# MT3620AvnetModule.net
KiCad netlist of a schematic drawn in Altium Designer
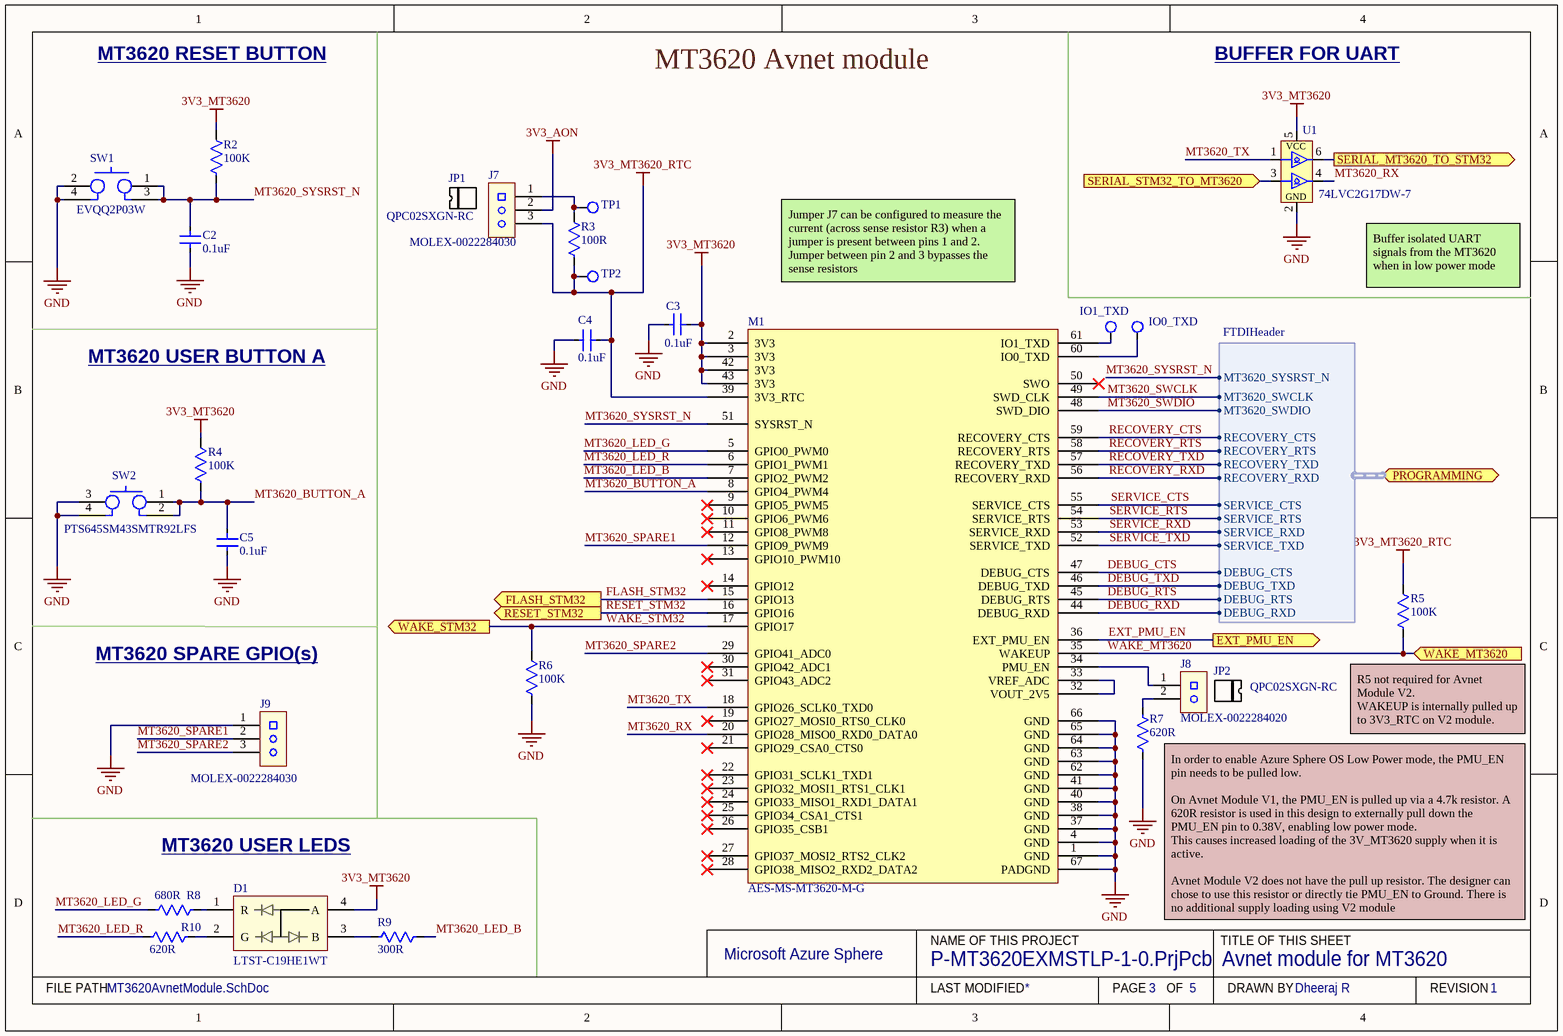
[diagram p0: MT3620AvnetModule.SchDoc]

(export (version "E")
  (design (tool "Eeschema 10.0.6"))
  (components
    (comp (ref "C2")
      (value "0.1uF")
      (footprint "CC0603")
      (description "0.1uF, 0603, CC0603KRX7R8BB104, Yageo, 25V, X7R, 10%, FULL REEL")
      (fields
        (field (name "MANUFACTURER") "Yageo")
        (field (name "MANUFACTURER PART NUMBER") "CC0603KRX7R8BB104")
      )
      (libsource (lib "Yageo") (part "CC0603KRX7R8BB104"))
    )
    (comp (ref "C3")
      (value "0.1uF")
      (footprint "CC0603")
      (description "0.1uF, 0603, CC0603KRX7R8BB104, Yageo, 25V, X7R, 10%, FULL REEL")
      (fields
        (field (name "MANUFACTURER") "Yageo")
        (field (name "MANUFACTURER PART NUMBER") "CC0603KRX7R8BB104")
      )
      (libsource (lib "Yageo") (part "CC0603KRX7R8BB104"))
    )
    (comp (ref "C4")
      (value "0.1uF")
      (footprint "CC0603")
      (description "0.1uF, 0603, CC0603KRX7R8BB104, Yageo, 25V, X7R, 10%, FULL REEL")
      (fields
        (field (name "MANUFACTURER") "Yageo")
        (field (name "MANUFACTURER PART NUMBER") "CC0603KRX7R8BB104")
      )
      (libsource (lib "Yageo") (part "CC0603KRX7R8BB104"))
    )
    (comp (ref "C5")
      (value "0.1uF")
      (footprint "CC0603")
      (description "0.1uF, 0603, CC0603KRX7R8BB104, Yageo, 25V, X7R, 10%, FULL REEL")
      (fields
        (field (name "MANUFACTURER") "Yageo")
        (field (name "MANUFACTURER PART NUMBER") "CC0603KRX7R8BB104")
      )
      (libsource (lib "Yageo") (part "CC0603KRX7R8BB104"))
    )
    (comp (ref "D1")
      (value "LTST-C19HE1WT")
      (footprint "LTST-C19HE1WT")
      (description "LED RGB DIFFUSED 0606 SMD")
      (fields (field (name "MANUFACTURER") "Lite-On Inc."))
      (libsource (lib "Lite-On") (part "LTST-C19HE1WT"))
    )
    (comp (ref "IO0_TXD")
      (value "TestPoint")
      (footprint "Pad1.27mm")
      (description "Test Point")
      (libsource (lib "generic") (part "TestPoint"))
    )
    (comp (ref "IO1_TXD")
      (value "TestPoint")
      (footprint "Pad1.27mm")
      (description "Test Point")
      (libsource (lib "generic") (part "TestPoint"))
    )
    (comp (ref "J7")
      (value "MOLEX-0022284030")
      (footprint "0022284030")
      (description "CONN HEADER 3POS .100 VERT TIN")
      (fields
        (field (name "MANUFACTURER") "Molex, LLC")
        (field (name "MANUFACTURER PART NUMBER") "0022284030")
      )
      (libsource (lib "") (part "MOLEX-0022284030_1"))
    )
    (comp (ref "J8")
      (value "MOLEX-0022284020")
      (footprint "0022284020")
      (description "CONN HEADER 2POS .100 VERT TIN")
      (fields
        (field (name "MANUFACTURER") "Molex, LLC")
        (field (name "MANUFACTURER PART NUMBER") "0022284020")
      )
      (libsource (lib "Molex") (part "MOLEX-0022284020"))
    )
    (comp (ref "J9")
      (value "MOLEX-0022284030")
      (footprint "0022284030")
      (description "CONN HEADER 3POS .100 VERT TIN")
      (fields
        (field (name "MANUFACTURER") "Molex, LLC")
        (field (name "MANUFACTURER PART NUMBER") "0022284030")
      )
      (libsource (lib "Molex") (part "MOLEX-0022284030"))
    )
    (comp (ref "JP1")
      (value "QPC02SXGN-RC")
      (description "CONN JUMPER SHORTING .100\" GOLD")
      (fields (field (name "MANUFACTURER") "Sullins"))
      (libsource (lib "") (part "QPC02SXGN-RC_1"))
    )
    (comp (ref "JP2")
      (value "QPC02SXGN-RC")
      (description "CONN JUMPER SHORTING .100\" GOLD")
      (fields (field (name "MANUFACTURER") "Sullins"))
      (libsource (lib "SullinsConnectorSolutions") (part "QPC02SXGN-RC"))
    )
    (comp (ref "M1")
      (value "AES-MS-MT3620-M-G")
      (footprint "AES-MS-MT3620-M-G")
      (libsource (lib "Avnet") (part "AES-MS-MT3620-M-G (SAT)"))
    )
    (comp (ref "R2")
      (value "100K")
      (footprint "VISHAY-0603")
      (description "100K Ohm 0603 1% 0.1W(1/10W) 100ppm Paper T/R")
      (fields
        (field (name "MANUFACTURER") "Yageo")
        (field (name "MANUFACTURER PART NUMBER") "RC0603FR-07100KL")
      )
      (libsource (lib "Yageo") (part "RC0603FR-07100KL"))
    )
    (comp (ref "R3")
      (value "100R")
      (footprint "VISHAY-0603")
      (description "100 OHM Current Sense 0.1% 1/2W 0603")
      (fields
        (field (name "MANUFACTURER") "Vishay Dale Thin Film")
        (field (name "MANUFACTURER PART NUMBER") "PCAN0603E1000BST5")
      )
      (libsource (lib "Vishay") (part "PCAN0603E1000BST5"))
    )
    (comp (ref "R4")
      (value "100K")
      (footprint "VISHAY-0603")
      (description "100K Ohm 0603 1% 0.1W(1/10W) 100ppm Paper T/R")
      (fields
        (field (name "MANUFACTURER") "Yageo")
        (field (name "MANUFACTURER PART NUMBER") "RC0603FR-07100KL")
      )
      (libsource (lib "Yageo") (part "RC0603FR-07100KL"))
    )
    (comp (ref "R5")
      (value "100K")
      (footprint "VISHAY-0603")
      (description "100K Ohm 0603 1% 0.1W(1/10W) 100ppm Paper T/R")
      (fields
        (field (name "MANUFACTURER") "Yageo")
        (field (name "MANUFACTURER PART NUMBER") "RC0603FR-07100KL")
      )
      (libsource (lib "Yageo") (part "RC0603FR-07100KL"))
    )
    (comp (ref "R6")
      (value "100K")
      (footprint "VISHAY-0603")
      (description "100K Ohm 0603 1% 0.1W(1/10W) 100ppm Paper T/R")
      (fields
        (field (name "MANUFACTURER") "Yageo")
        (field (name "MANUFACTURER PART NUMBER") "RC0603FR-07100KL")
      )
      (libsource (lib "Yageo") (part "RC0603FR-07100KL"))
    )
    (comp (ref "R7")
      (value "620R")
      (footprint "RC0603")
      (description "620 Ohm, 0603, 1% 0.1W(1/10W) 100ppm/ C Molded SMD Paper T/R")
      (fields
        (field (name "MANUFACTURER") "Yageo")
        (field (name "MANUFACTURER PART NUMBER") "RC0603FR-07620RL")
      )
      (libsource (lib "Yageo") (part "RC0603FR-07620RL"))
    )
    (comp (ref "R8")
      (value "680R")
      (footprint "RC0603")
      (description "680R, 0603 YAGEO - RC0603FR-07680RL - SMD Chip Resistor, RC Series, 50 V, Thick Film, 100 mW")
      (fields
        (field (name "MANUFACTURER") "Yageo")
        (field (name "MANUFACTURER PART NUMBER") "RC0603FR-07680RL")
      )
      (libsource (lib "Yageo") (part "RC0603FR-07680RL"))
    )
    (comp (ref "R9")
      (value "300R")
      (footprint "RC0603")
      (description "300 Ohm, 0603, 1% 0.1W(1/10W) 100ppm/ C Molded SMD Paper T/R")
      (fields
        (field (name "MANUFACTURER") "Yageo")
        (field (name "MANUFACTURER PART NUMBER") "RC0603FR-07300RL")
      )
      (libsource (lib "Yageo") (part "RC0603FR-07300RL"))
    )
    (comp (ref "R10")
      (value "620R")
      (footprint "RC0603")
      (description "620 Ohm, 0603, 1% 0.1W(1/10W) 100ppm/ C Molded SMD Paper T/R")
      (fields
        (field (name "MANUFACTURER") "Yageo")
        (field (name "MANUFACTURER PART NUMBER") "RC0603FR-07620RL")
      )
      (libsource (lib "Yageo") (part "RC0603FR-07620RL"))
    )
    (comp (ref "SW1")
      (value "SWI TACT SPN0 PANASONIC EVQQ2P03W")
      (footprint "EVQQ2P03W")
      (description "PANASONIC - EVQQ2P03W - SWITCH, SPNO, SMD")
      (fields (field (name "MANUFACTURER") "PANASONIC") (field (name "MANUFACTURER PART NUMBER") "EVQQ2P03W"))
      (libsource (lib "switch") (part "SWI TACT SPN0 PANASONIC EVQQ2P03W"))
    )
    (comp (ref "SW2")
      (value "PTS645SM43SMTR92LFS")
      (footprint "C&K PTS645SM43SMTR92LFS")
      (description "SWITCH TACTILE SPST-NO 0.05A 12V")
      (fields (field (name "MANUFACTURER") "ITT C&K"))
      (libsource (lib "C&K") (part "PTS645SM43SMTR92LFS"))
    )
    (comp (ref "TP1")
      (value "TestPointHole")
      (footprint "PTH1.27mm-0.9mm")
      (description "Test Point With Hole")
      (libsource (lib "generic") (part "TestPointHole"))
    )
    (comp (ref "TP2")
      (value "TestPointHole")
      (footprint "PTH1.27mm-0.9mm")
      (description "Test Point With Hole")
      (libsource (lib "generic") (part "TestPointHole"))
    )
    (comp (ref "U1")
      (value "74LVC2G17DW-7")
      (footprint "Nexperia-SOT363")
      (description "Buffers & Line Drivers LVC 2 Gates LOGIC")
      (fields (field (name "MANUFACTURER") "Diodes"))
      (libsource (lib "DiodesInc") (part "74LVC2G17DW-7"))
    )
  )
  (nets
    (net (code "2") (name "/DEBUG_CTS") (class "Default")
      (node (ref "M1") (pin "47") (pinfunction "DEBUG_CTS_47") (pintype "passive"))
    )
    (net (code "3") (name "/DEBUG_RTS") (class "Default")
      (node (ref "M1") (pin "45") (pinfunction "DEBUG_RTS_45") (pintype "passive"))
    )
    (net (code "4") (name "/DEBUG_RXD") (class "Default")
      (node (ref "M1") (pin "44") (pinfunction "DEBUG_RXD_44") (pintype "passive"))
    )
    (net (code "5") (name "/DEBUG_TXD") (class "Default")
      (node (ref "M1") (pin "46") (pinfunction "DEBUG_TXD_46") (pintype "passive"))
    )
    (net (code "6") (name "/EXT_PMU_EN") (class "Default")
      (node (ref "M1") (pin "36") (pinfunction "EXT_PMU_EN_36") (pintype "passive"))
    )
    (net (code "7") (name "/FLASH_STM32") (class "Default")
      (node (ref "M1") (pin "15") (pinfunction "GPIO13_15") (pintype "passive"))
    )
    (net (code "8") (name "/MT3620_BUTTON_A") (class "Default")
      (node (ref "C5") (pin "2") (pinfunction "2_2") (pintype "passive"))
      (node (ref "M1") (pin "8") (pinfunction "GPIO4_PWM4_8") (pintype "passive"))
      (node (ref "R4") (pin "1") (pinfunction "1_1") (pintype "passive"))
      (node (ref "SW2") (pin "1") (pinfunction "1_1") (pintype "passive"))
      (node (ref "SW2") (pin "2") (pinfunction "2_2") (pintype "passive"))
    )
    (net (code "9") (name "/MT3620_LED_B") (class "Default")
      (node (ref "M1") (pin "7") (pinfunction "GPIO2_PWM2_7") (pintype "passive"))
      (node (ref "R9") (pin "2") (pinfunction "2_2") (pintype "passive"))
    )
    (net (code "10") (name "/MT3620_LED_G") (class "Default")
      (node (ref "M1") (pin "5") (pinfunction "GPIO0_PWM0_5") (pintype "passive"))
      (node (ref "R8") (pin "1") (pinfunction "1_1") (pintype "passive"))
    )
    (net (code "11") (name "/MT3620_LED_R") (class "Default")
      (node (ref "M1") (pin "6") (pinfunction "GPIO1_PWM1_6") (pintype "passive"))
      (node (ref "R10") (pin "1") (pinfunction "1_1") (pintype "passive"))
    )
    (net (code "12") (name "/MT3620_RX") (class "Default")
      (node (ref "M1") (pin "20") (pinfunction "GPIO28_MISO0_RXD0_DATA0_20") (pintype "passive"))
      (node (ref "U1") (pin "4") (pinfunction "4_4") (pintype "passive"))
    )
    (net (code "13") (name "/MT3620_SPARE1") (class "Default")
      (node (ref "J9") (pin "2") (pinfunction "2_2") (pintype "passive"))
      (node (ref "M1") (pin "12") (pinfunction "GPIO9_PWM9_12") (pintype "passive"))
    )
    (net (code "14") (name "/MT3620_SPARE2") (class "Default")
      (node (ref "J9") (pin "3") (pinfunction "3_3") (pintype "passive"))
      (node (ref "M1") (pin "29") (pinfunction "GPIO41_ADC0_29") (pintype "passive"))
    )
    (net (code "15") (name "/MT3620_SWCLK") (class "Default")
      (node (ref "M1") (pin "49") (pinfunction "SWD_CLK_49") (pintype "passive"))
    )
    (net (code "16") (name "/MT3620_SWDIO") (class "Default")
      (node (ref "M1") (pin "48") (pinfunction "SWD_DIO_48") (pintype "passive"))
    )
    (net (code "17") (name "/MT3620_SYSRST_N") (class "Default")
      (node (ref "C2") (pin "2") (pinfunction "2_2") (pintype "passive"))
      (node (ref "M1") (pin "51") (pinfunction "SYSRST_N_51") (pintype "passive"))
      (node (ref "R2") (pin "1") (pinfunction "1_1") (pintype "passive"))
      (node (ref "SW1") (pin "1") (pinfunction "1_1") (pintype "passive"))
      (node (ref "SW1") (pin "3") (pinfunction "3_3") (pintype "passive"))
    )
    (net (code "18") (name "/MT3620_TX") (class "Default")
      (node (ref "M1") (pin "18") (pinfunction "GPIO26_SCLK0_TXD0_18") (pintype "passive"))
      (node (ref "U1") (pin "1") (pinfunction "1_1") (pintype "passive"))
    )
    (net (code "19") (name "/RECOVERY_CTS") (class "Default")
      (node (ref "M1") (pin "59") (pinfunction "RECOVERY_CTS_59") (pintype "passive"))
    )
    (net (code "20") (name "/RECOVERY_RTS") (class "Default")
      (node (ref "M1") (pin "58") (pinfunction "RECOVERY_RTS_58") (pintype "passive"))
    )
    (net (code "21") (name "/RECOVERY_RXD") (class "Default")
      (node (ref "M1") (pin "56") (pinfunction "RECOVERY_RXD_56") (pintype "passive"))
    )
    (net (code "22") (name "/RECOVERY_TXD") (class "Default")
      (node (ref "M1") (pin "57") (pinfunction "RECOVERY_TXD_57") (pintype "passive"))
    )
    (net (code "23") (name "/RESET_STM32") (class "Default")
      (node (ref "M1") (pin "16") (pinfunction "GPIO16_16") (pintype "passive"))
    )
    (net (code "24") (name "/SERIAL_MT3620_TO_STM32") (class "Default")
      (node (ref "U1") (pin "6") (pinfunction "6_6") (pintype "passive"))
    )
    (net (code "25") (name "/SERIAL_STM32_TO_MT3620") (class "Default")
      (node (ref "U1") (pin "3") (pinfunction "3_3") (pintype "passive"))
    )
    (net (code "26") (name "/SERVICE_CTS") (class "Default")
      (node (ref "M1") (pin "55") (pinfunction "SERVICE_CTS_55") (pintype "passive"))
    )
    (net (code "27") (name "/SERVICE_RTS") (class "Default")
      (node (ref "M1") (pin "54") (pinfunction "SERVICE_RTS_54") (pintype "passive"))
    )
    (net (code "28") (name "/SERVICE_RXD") (class "Default")
      (node (ref "M1") (pin "53") (pinfunction "SERVICE_RXD_53") (pintype "passive"))
    )
    (net (code "29") (name "/SERVICE_TXD") (class "Default")
      (node (ref "M1") (pin "52") (pinfunction "SERVICE_TXD_52") (pintype "passive"))
    )
    (net (code "30") (name "/WAKE_MT3620") (class "Default")
      (node (ref "M1") (pin "35") (pinfunction "WAKEUP_35") (pintype "passive"))
      (node (ref "R5") (pin "1") (pinfunction "1_1") (pintype "passive"))
    )
    (net (code "31") (name "/WAKE_STM32") (class "Default")
      (node (ref "M1") (pin "17") (pinfunction "GPIO17_17") (pintype "passive"))
      (node (ref "R6") (pin "2") (pinfunction "2_2") (pintype "passive"))
    )
    (net (code "33") (name "3V3_AON") (class "Default")
      (node (ref "J7") (pin "2") (pinfunction "2_2") (pintype "passive"))
    )
    (net (code "34") (name "3V3_MT3620") (class "Default")
      (node (ref "C3") (pin "2") (pinfunction "2_2") (pintype "passive"))
      (node (ref "D1") (pin "4") (pinfunction "A_4") (pintype "passive"))
      (node (ref "M1") (pin "2") (pinfunction "3V3_2") (pintype "passive"))
      (node (ref "M1") (pin "3") (pinfunction "3V3_3") (pintype "passive"))
      (node (ref "M1") (pin "42") (pinfunction "3V3_42") (pintype "passive"))
      (node (ref "M1") (pin "43") (pinfunction "3V3_43") (pintype "passive"))
      (node (ref "R2") (pin "2") (pinfunction "2_2") (pintype "passive"))
      (node (ref "R4") (pin "2") (pinfunction "2_2") (pintype "passive"))
      (node (ref "U1") (pin "5") (pinfunction "5_5") (pintype "passive"))
    )
    (net (code "35") (name "3V3_MT3620_RTC") (class "Default")
      (node (ref "C4") (pin "2") (pinfunction "2_2") (pintype "passive"))
      (node (ref "J7") (pin "3") (pinfunction "3_3") (pintype "passive"))
      (node (ref "M1") (pin "39") (pinfunction "3V3_RTC_39") (pintype "passive"))
      (node (ref "R3") (pin "2") (pinfunction "2_2") (pintype "passive"))
      (node (ref "R5") (pin "2") (pinfunction "2_2") (pintype "passive"))
      (node (ref "TP2") (pin "1") (pinfunction "1_1") (pintype "passive"))
    )
    (net (code "36") (name "GND") (class "Default")
      (node (ref "C2") (pin "1") (pinfunction "1_1") (pintype "passive"))
      (node (ref "C3") (pin "1") (pinfunction "1_1") (pintype "passive"))
      (node (ref "C4") (pin "1") (pinfunction "1_1") (pintype "passive"))
      (node (ref "C5") (pin "1") (pinfunction "1_1") (pintype "passive"))
      (node (ref "J9") (pin "1") (pinfunction "1_1") (pintype "passive"))
      (node (ref "M1") (pin "1") (pinfunction "GND_1") (pintype "passive"))
      (node (ref "M1") (pin "37") (pinfunction "GND_37") (pintype "passive"))
      (node (ref "M1") (pin "38") (pinfunction "GND_38") (pintype "passive"))
      (node (ref "M1") (pin "4") (pinfunction "GND_4") (pintype "passive"))
      (node (ref "M1") (pin "40") (pinfunction "GND_40") (pintype "passive"))
      (node (ref "M1") (pin "41") (pinfunction "GND_41") (pintype "passive"))
      (node (ref "M1") (pin "62") (pinfunction "GND_62") (pintype "passive"))
      (node (ref "M1") (pin "63") (pinfunction "GND_63") (pintype "passive"))
      (node (ref "M1") (pin "64") (pinfunction "GND_64") (pintype "passive"))
      (node (ref "M1") (pin "65") (pinfunction "GND_65") (pintype "passive"))
      (node (ref "M1") (pin "66") (pinfunction "GND_66") (pintype "passive"))
      (node (ref "M1") (pin "67") (pinfunction "PADGND_67") (pintype "passive"))
      (node (ref "R6") (pin "1") (pinfunction "1_1") (pintype "passive"))
      (node (ref "R7") (pin "1") (pinfunction "1_1") (pintype "passive"))
      (node (ref "SW1") (pin "2") (pinfunction "2_2") (pintype "passive"))
      (node (ref "SW1") (pin "4") (pinfunction "4_4") (pintype "passive"))
      (node (ref "SW2") (pin "3") (pinfunction "3_3") (pintype "passive"))
      (node (ref "SW2") (pin "4") (pinfunction "4_4") (pintype "passive"))
      (node (ref "U1") (pin "2") (pinfunction "2_2") (pintype "passive"))
    )
    (net (code "37") (name "Net-(D1-B)") (class "Default")
      (node (ref "D1") (pin "3") (pinfunction "B_3") (pintype "passive"))
      (node (ref "R9") (pin "1") (pinfunction "1_1") (pintype "passive"))
    )
    (net (code "38") (name "Net-(D1-G)") (class "Default")
      (node (ref "D1") (pin "2") (pinfunction "G_2") (pintype "passive"))
      (node (ref "R10") (pin "2") (pinfunction "2_2") (pintype "passive"))
    )
    (net (code "39") (name "Net-(D1-R)") (class "Default")
      (node (ref "D1") (pin "1") (pinfunction "R_1") (pintype "passive"))
      (node (ref "R8") (pin "2") (pinfunction "2_2") (pintype "passive"))
    )
    (net (code "40") (name "Net-(J7-Pad1)") (class "Default")
      (node (ref "J7") (pin "1") (pinfunction "1_1") (pintype "passive"))
      (node (ref "R3") (pin "1") (pinfunction "1_1") (pintype "passive"))
      (node (ref "TP1") (pin "1") (pinfunction "1_1") (pintype "passive"))
    )
    (net (code "41") (name "Net-(J8-Pad2)") (class "Default")
      (node (ref "J8") (pin "2") (pinfunction "2_2") (pintype "passive"))
      (node (ref "R7") (pin "2") (pinfunction "2_2") (pintype "passive"))
    )
    (net (code "42") (name "Net-(M1-IO0_TXD)") (class "Default")
      (node (ref "IO0_TXD") (pin "1") (pinfunction "1_1") (pintype "passive"))
      (node (ref "M1") (pin "60") (pinfunction "IO0_TXD_60") (pintype "passive"))
    )
    (net (code "43") (name "Net-(M1-IO1_TXD)") (class "Default")
      (node (ref "IO1_TXD") (pin "1") (pinfunction "1_1") (pintype "passive"))
      (node (ref "M1") (pin "61") (pinfunction "IO1_TXD_61") (pintype "passive"))
    )
    (net (code "44") (name "Net-(M1-PMU_EN)") (class "Default")
      (node (ref "J8") (pin "1") (pinfunction "1_1") (pintype "passive"))
      (node (ref "M1") (pin "34") (pinfunction "PMU_EN_34") (pintype "passive"))
    )
    (net (code "45") (name "Net-(M1-VOUT_2V5)") (class "Default")
      (node (ref "M1") (pin "32") (pinfunction "VOUT_2V5_32") (pintype "passive"))
      (node (ref "M1") (pin "33") (pinfunction "VREF_ADC_33") (pintype "passive"))
    )
    (net (code "46") (name "unconnected-(M1-GPIO5_PWM5-Pad9)") (class "Default")
      (node (ref "M1") (pin "9") (pinfunction "GPIO5_PWM5_9") (pintype "passive+no_connect"))
    )
    (net (code "47") (name "unconnected-(M1-GPIO6_PWM6-Pad10)") (class "Default")
      (node (ref "M1") (pin "10") (pinfunction "GPIO6_PWM6_10") (pintype "passive+no_connect"))
    )
    (net (code "48") (name "unconnected-(M1-GPIO8_PWM8-Pad11)") (class "Default")
      (node (ref "M1") (pin "11") (pinfunction "GPIO8_PWM8_11") (pintype "passive+no_connect"))
    )
    (net (code "49") (name "unconnected-(M1-GPIO10_PWM10-Pad13)") (class "Default")
      (node (ref "M1") (pin "13") (pinfunction "GPIO10_PWM10_13") (pintype "passive+no_connect"))
    )
    (net (code "50") (name "unconnected-(M1-GPIO12-Pad14)") (class "Default")
      (node (ref "M1") (pin "14") (pinfunction "GPIO12_14") (pintype "passive+no_connect"))
    )
    (net (code "51") (name "unconnected-(M1-GPIO27_MOSI0_RTS0_CLK0-Pad19)") (class "Default")
      (node (ref "M1") (pin "19") (pinfunction "GPIO27_MOSI0_RTS0_CLK0_19") (pintype "passive+no_connect"))
    )
    (net (code "52") (name "unconnected-(M1-GPIO29_CSA0_CTS0-Pad21)") (class "Default")
      (node (ref "M1") (pin "21") (pinfunction "GPIO29_CSA0_CTS0_21") (pintype "passive+no_connect"))
    )
    (net (code "53") (name "unconnected-(M1-GPIO31_SCLK1_TXD1-Pad22)") (class "Default")
      (node (ref "M1") (pin "22") (pinfunction "GPIO31_SCLK1_TXD1_22") (pintype "passive+no_connect"))
    )
    (net (code "54") (name "unconnected-(M1-GPIO32_MOSI1_RTS1_CLK1-Pad23)") (class "Default")
      (node (ref "M1") (pin "23") (pinfunction "GPIO32_MOSI1_RTS1_CLK1_23") (pintype "passive+no_connect"))
    )
    (net (code "55") (name "unconnected-(M1-GPIO33_MISO1_RXD1_DATA1-Pad24)") (class "Default")
      (node (ref "M1") (pin "24") (pinfunction "GPIO33_MISO1_RXD1_DATA1_24") (pintype "passive+no_connect"))
    )
    (net (code "56") (name "unconnected-(M1-GPIO34_CSA1_CTS1-Pad25)") (class "Default")
      (node (ref "M1") (pin "25") (pinfunction "GPIO34_CSA1_CTS1_25") (pintype "passive+no_connect"))
    )
    (net (code "57") (name "unconnected-(M1-GPIO35_CSB1-Pad26)") (class "Default")
      (node (ref "M1") (pin "26") (pinfunction "GPIO35_CSB1_26") (pintype "passive+no_connect"))
    )
    (net (code "58") (name "unconnected-(M1-GPIO37_MOSI2_RTS2_CLK2-Pad27)") (class "Default")
      (node (ref "M1") (pin "27") (pinfunction "GPIO37_MOSI2_RTS2_CLK2_27") (pintype "passive+no_connect"))
    )
    (net (code "59") (name "unconnected-(M1-GPIO38_MISO2_RXD2_DATA2-Pad28)") (class "Default")
      (node (ref "M1") (pin "28") (pinfunction "GPIO38_MISO2_RXD2_DATA2_28") (pintype "passive+no_connect"))
    )
    (net (code "60") (name "unconnected-(M1-GPIO42_ADC1-Pad30)") (class "Default")
      (node (ref "M1") (pin "30") (pinfunction "GPIO42_ADC1_30") (pintype "passive+no_connect"))
    )
    (net (code "61") (name "unconnected-(M1-GPIO43_ADC2-Pad31)") (class "Default")
      (node (ref "M1") (pin "31") (pinfunction "GPIO43_ADC2_31") (pintype "passive+no_connect"))
    )
    (net (code "62") (name "unconnected-(M1-SWO-Pad50)") (class "Default")
      (node (ref "M1") (pin "50") (pinfunction "SWO_50") (pintype "passive+no_connect"))
    )
  )
)
